# untitled.net
KiCad netlist of a schematic drawn in EAGLE
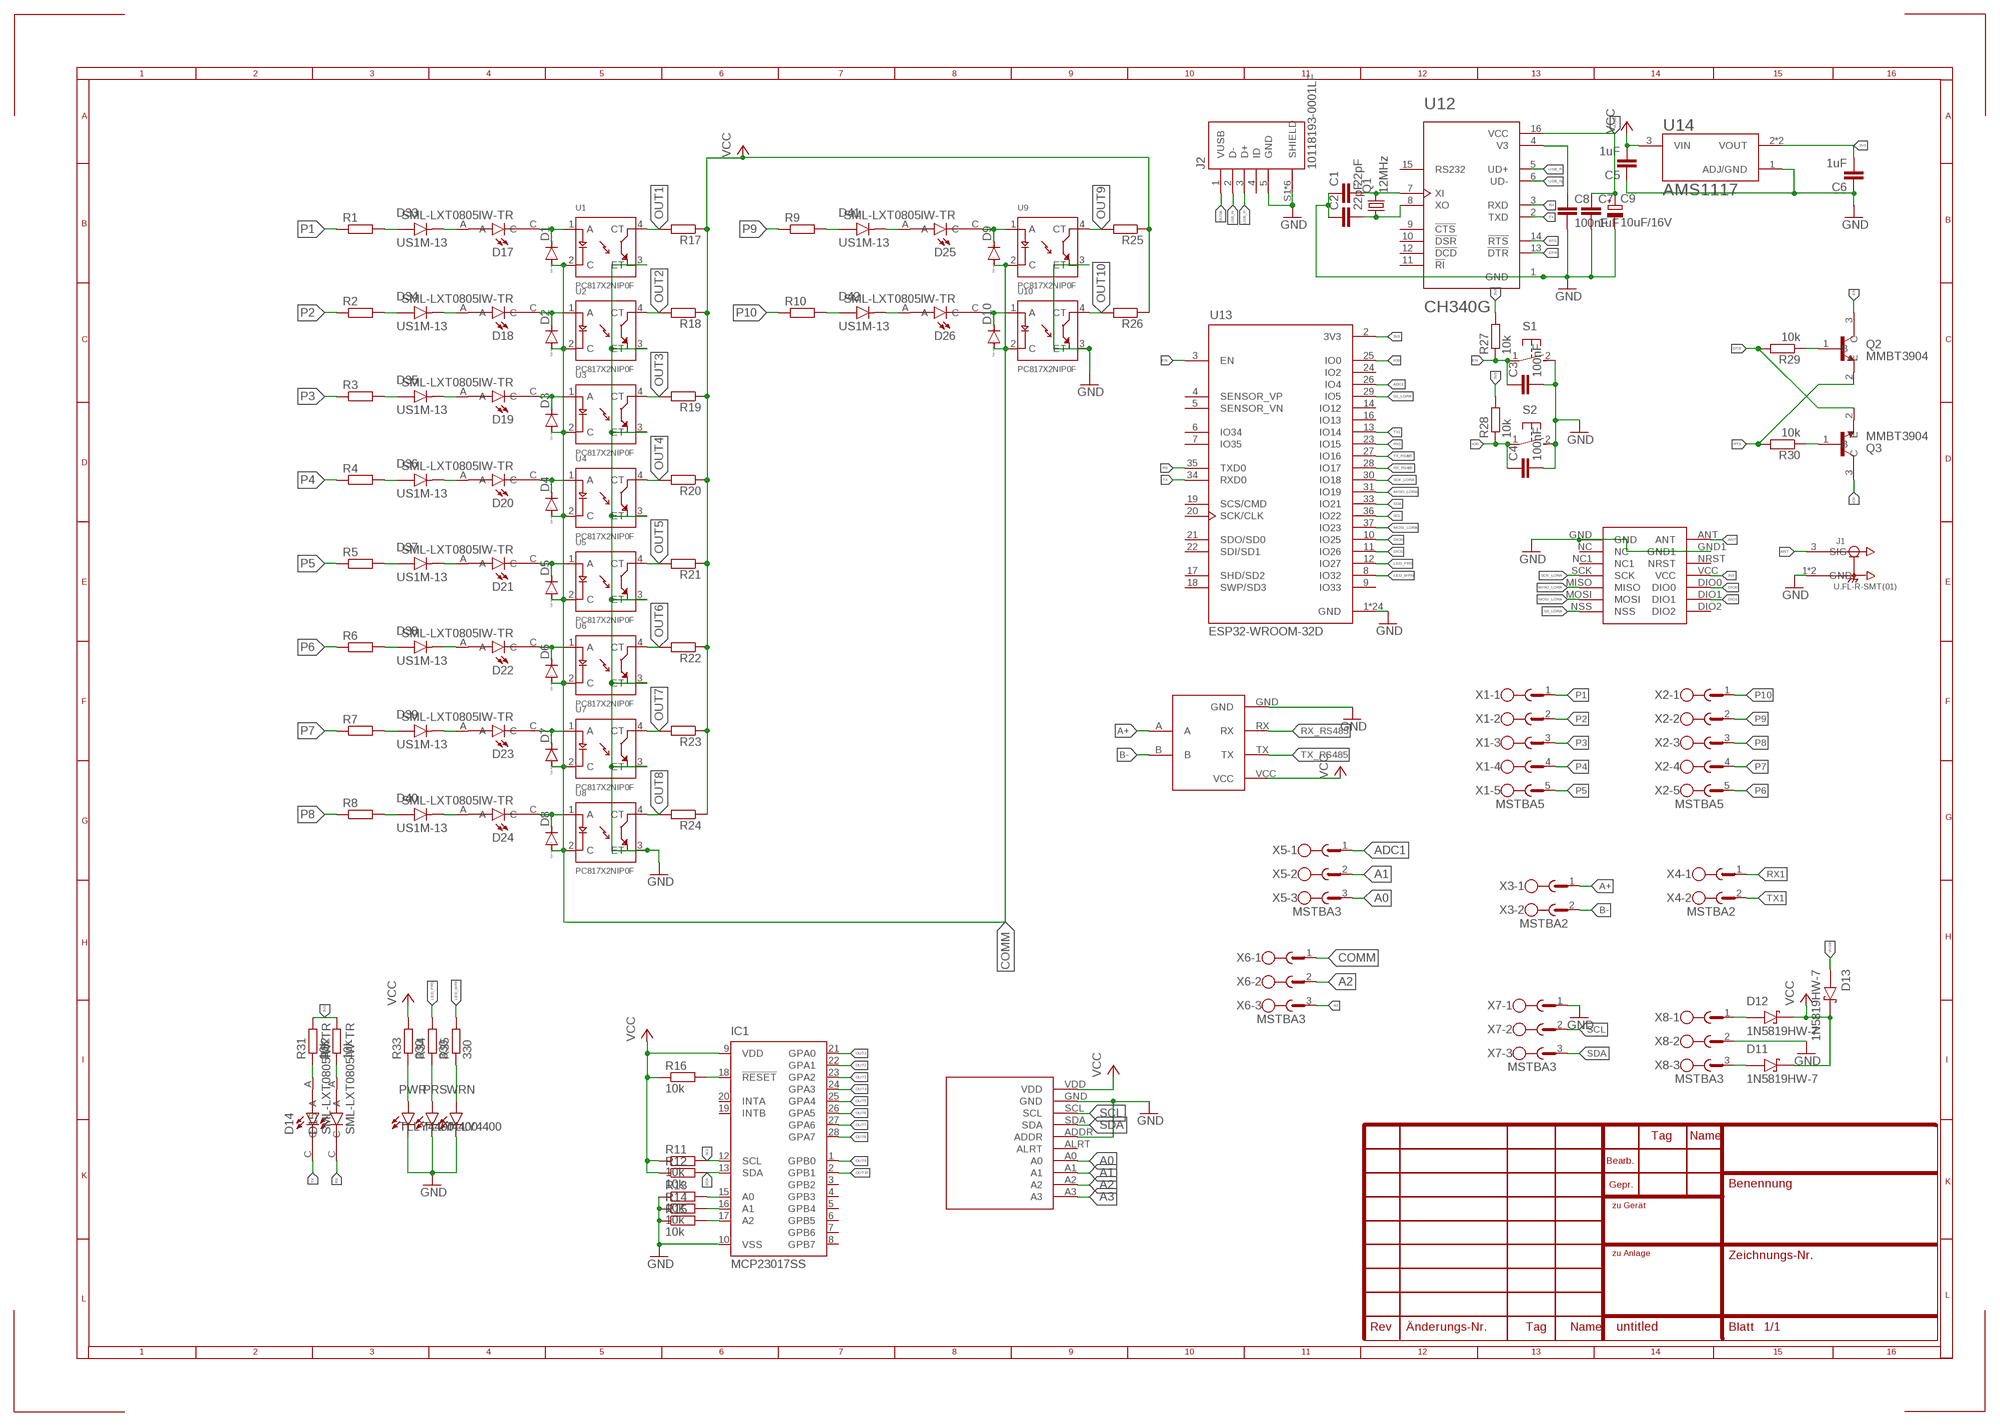
[diagram p0: schematic, sheet 1]

(export (version "E")
  (design (tool "Eeschema 10.0.6"))
  (components
    (comp (ref "ADS1")
      (value "ADS1115")
      (footprint "eagle-import:ADS1115")
      (libsource (lib "eagle-import") (part "ADS1115"))
    )
    (comp (ref "C1")
      (value "22pF")
      (footprint "eagle-import:C0805K")
      (libsource (lib "eagle-import") (part "C-EUC0805K"))
    )
    (comp (ref "C2")
      (value "22pF")
      (footprint "eagle-import:C0805K")
      (libsource (lib "eagle-import") (part "C-EUC0805K"))
    )
    (comp (ref "C3")
      (value "100nF")
      (footprint "eagle-import:C0805K")
      (libsource (lib "eagle-import") (part "C-EUC0805K"))
    )
    (comp (ref "C4")
      (value "100nF")
      (footprint "eagle-import:C0805K")
      (libsource (lib "eagle-import") (part "C-EUC0805K"))
    )
    (comp (ref "C5")
      (value "1uF")
      (footprint "eagle-import:C0805K")
      (libsource (lib "eagle-import") (part "C-EUC0805K"))
    )
    (comp (ref "C6")
      (value "1uF")
      (footprint "eagle-import:C0805K")
      (libsource (lib "eagle-import") (part "C-EUC0805K"))
    )
    (comp (ref "C7")
      (value "1uF")
      (footprint "eagle-import:C0805K")
      (libsource (lib "eagle-import") (part "C-EUC0805K"))
    )
    (comp (ref "C8")
      (value "100nF")
      (footprint "eagle-import:C0805K")
      (libsource (lib "eagle-import") (part "C-EUC0805K"))
    )
    (comp (ref "C9")
      (value "10uF/16V")
      (footprint "eagle-import:153CLV-0505")
      (libsource (lib "eagle-import") (part "CPOL-EU153CLV-0505"))
    )
    (comp (ref "D1")
      (value "DIODE-SOD123")
      (footprint "eagle-import:SOD123")
      (libsource (lib "eagle-import") (part "DIODE-SOD123"))
    )
    (comp (ref "D2")
      (value "DIODE-SOD123")
      (footprint "eagle-import:SOD123")
      (libsource (lib "eagle-import") (part "DIODE-SOD123"))
    )
    (comp (ref "D3")
      (value "DIODE-SOD123")
      (footprint "eagle-import:SOD123")
      (libsource (lib "eagle-import") (part "DIODE-SOD123"))
    )
    (comp (ref "D4")
      (value "DIODE-SOD123")
      (footprint "eagle-import:SOD123")
      (libsource (lib "eagle-import") (part "DIODE-SOD123"))
    )
    (comp (ref "D5")
      (value "DIODE-SOD123")
      (footprint "eagle-import:SOD123")
      (libsource (lib "eagle-import") (part "DIODE-SOD123"))
    )
    (comp (ref "D6")
      (value "DIODE-SOD123")
      (footprint "eagle-import:SOD123")
      (libsource (lib "eagle-import") (part "DIODE-SOD123"))
    )
    (comp (ref "D7")
      (value "DIODE-SOD123")
      (footprint "eagle-import:SOD123")
      (libsource (lib "eagle-import") (part "DIODE-SOD123"))
    )
    (comp (ref "D8")
      (value "DIODE-SOD123")
      (footprint "eagle-import:SOD123")
      (libsource (lib "eagle-import") (part "DIODE-SOD123"))
    )
    (comp (ref "D9")
      (value "DIODE-SOD123")
      (footprint "eagle-import:SOD123")
      (libsource (lib "eagle-import") (part "DIODE-SOD123"))
    )
    (comp (ref "D10")
      (value "DIODE-SOD123")
      (footprint "eagle-import:SOD123")
      (libsource (lib "eagle-import") (part "DIODE-SOD123"))
    )
    (comp (ref "D11")
      (value "1N5819HW-7")
      (footprint "eagle-import:SOD3715X145N")
      (fields (field (name "MF") "Diodes Inc."))
      (libsource (lib "eagle-import") (part "1N5819HW-7"))
    )
    (comp (ref "D12")
      (value "1N5819HW-7")
      (footprint "eagle-import:SOD3715X145N")
      (fields (field (name "MF") "Diodes Inc."))
      (libsource (lib "eagle-import") (part "1N5819HW-7"))
    )
    (comp (ref "D13")
      (value "1N5819HW-7")
      (footprint "eagle-import:SOD3715X145N")
      (fields (field (name "MF") "Diodes Inc."))
      (libsource (lib "eagle-import") (part "1N5819HW-7"))
    )
    (comp (ref "D14")
      (value "SML-LXT0805IW-TR")
      (footprint "eagle-import:LEDC2012X120N")
      (fields (field (name "MF") "Lumex Opto/Components"))
      (libsource (lib "eagle-import") (part "SML-LXT0805IW-TR"))
    )
    (comp (ref "D15")
      (value "SML-LXT0805IW-TR")
      (footprint "eagle-import:LEDC2012X120N")
      (fields (field (name "MF") "Lumex Opto/Components"))
      (libsource (lib "eagle-import") (part "SML-LXT0805IW-TR"))
    )
    (comp (ref "D17")
      (value "SML-LXT0805IW-TR")
      (footprint "eagle-import:LEDC2012X120N")
      (fields (field (name "MF") "Lumex Opto/Components"))
      (libsource (lib "eagle-import") (part "SML-LXT0805IW-TR"))
    )
    (comp (ref "D18")
      (value "SML-LXT0805IW-TR")
      (footprint "eagle-import:LEDC2012X120N")
      (fields (field (name "MF") "Lumex Opto/Components"))
      (libsource (lib "eagle-import") (part "SML-LXT0805IW-TR"))
    )
    (comp (ref "D19")
      (value "SML-LXT0805IW-TR")
      (footprint "eagle-import:LEDC2012X120N")
      (fields (field (name "MF") "Lumex Opto/Components"))
      (libsource (lib "eagle-import") (part "SML-LXT0805IW-TR"))
    )
    (comp (ref "D20")
      (value "SML-LXT0805IW-TR")
      (footprint "eagle-import:LEDC2012X120N")
      (fields (field (name "MF") "Lumex Opto/Components"))
      (libsource (lib "eagle-import") (part "SML-LXT0805IW-TR"))
    )
    (comp (ref "D21")
      (value "SML-LXT0805IW-TR")
      (footprint "eagle-import:LEDC2012X120N")
      (fields (field (name "MF") "Lumex Opto/Components"))
      (libsource (lib "eagle-import") (part "SML-LXT0805IW-TR"))
    )
    (comp (ref "D22")
      (value "SML-LXT0805IW-TR")
      (footprint "eagle-import:LEDC2012X120N")
      (fields (field (name "MF") "Lumex Opto/Components"))
      (libsource (lib "eagle-import") (part "SML-LXT0805IW-TR"))
    )
    (comp (ref "D23")
      (value "SML-LXT0805IW-TR")
      (footprint "eagle-import:LEDC2012X120N")
      (fields (field (name "MF") "Lumex Opto/Components"))
      (libsource (lib "eagle-import") (part "SML-LXT0805IW-TR"))
    )
    (comp (ref "D24")
      (value "SML-LXT0805IW-TR")
      (footprint "eagle-import:LEDC2012X120N")
      (fields (field (name "MF") "Lumex Opto/Components"))
      (libsource (lib "eagle-import") (part "SML-LXT0805IW-TR"))
    )
    (comp (ref "D25")
      (value "SML-LXT0805IW-TR")
      (footprint "eagle-import:LEDC2012X120N")
      (fields (field (name "MF") "Lumex Opto/Components"))
      (libsource (lib "eagle-import") (part "SML-LXT0805IW-TR"))
    )
    (comp (ref "D26")
      (value "SML-LXT0805IW-TR")
      (footprint "eagle-import:LEDC2012X120N")
      (fields (field (name "MF") "Lumex Opto/Components"))
      (libsource (lib "eagle-import") (part "SML-LXT0805IW-TR"))
    )
    (comp (ref "D33")
      (value "US1M-13")
      (footprint "eagle-import:DIOM5226X240N")
      (fields (field (name "MF") "Diodes Incorporated"))
      (libsource (lib "eagle-import") (part "US1M-13"))
    )
    (comp (ref "D34")
      (value "US1M-13")
      (footprint "eagle-import:DIOM5226X240N")
      (fields (field (name "MF") "Diodes Incorporated"))
      (libsource (lib "eagle-import") (part "US1M-13"))
    )
    (comp (ref "D35")
      (value "US1M-13")
      (footprint "eagle-import:DIOM5226X240N")
      (fields (field (name "MF") "Diodes Incorporated"))
      (libsource (lib "eagle-import") (part "US1M-13"))
    )
    (comp (ref "D36")
      (value "US1M-13")
      (footprint "eagle-import:DIOM5226X240N")
      (fields (field (name "MF") "Diodes Incorporated"))
      (libsource (lib "eagle-import") (part "US1M-13"))
    )
    (comp (ref "D37")
      (value "US1M-13")
      (footprint "eagle-import:DIOM5226X240N")
      (fields (field (name "MF") "Diodes Incorporated"))
      (libsource (lib "eagle-import") (part "US1M-13"))
    )
    (comp (ref "D38")
      (value "US1M-13")
      (footprint "eagle-import:DIOM5226X240N")
      (fields (field (name "MF") "Diodes Incorporated"))
      (libsource (lib "eagle-import") (part "US1M-13"))
    )
    (comp (ref "D39")
      (value "US1M-13")
      (footprint "eagle-import:DIOM5226X240N")
      (fields (field (name "MF") "Diodes Incorporated"))
      (libsource (lib "eagle-import") (part "US1M-13"))
    )
    (comp (ref "D40")
      (value "US1M-13")
      (footprint "eagle-import:DIOM5226X240N")
      (fields (field (name "MF") "Diodes Incorporated"))
      (libsource (lib "eagle-import") (part "US1M-13"))
    )
    (comp (ref "D41")
      (value "US1M-13")
      (footprint "eagle-import:DIOM5226X240N")
      (fields (field (name "MF") "Diodes Incorporated"))
      (libsource (lib "eagle-import") (part "US1M-13"))
    )
    (comp (ref "D42")
      (value "US1M-13")
      (footprint "eagle-import:DIOM5226X240N")
      (fields (field (name "MF") "Diodes Incorporated"))
      (libsource (lib "eagle-import") (part "US1M-13"))
    )
    (comp (ref "IC1")
      (value "MCP23017SS")
      (footprint "eagle-import:SSOP28")
      (fields (field (name "MF") "MICROCHIP") (field (name "MPN") "MCP23017-E/SS"))
      (libsource (lib "eagle-import") (part "MCP23017SS"))
    )
    (comp (ref "J1")
      (value "U.FL-R-SMT(01)")
      (footprint "eagle-import:HRS_U.FL-R-SMT(01)")
      (fields (field (name "MF") "Hirose"))
      (libsource (lib "eagle-import") (part "U.FL-R-SMT(01)"))
    )
    (comp (ref "J2")
      (value "10118193-0001LF")
      (footprint "eagle-import:FCI_10118193-0001LF")
      (fields (field (name "MF") "FCI"))
      (libsource (lib "eagle-import") (part "10118193-0001LF"))
    )
    (comp (ref "LORA-NICERF-V1")
      (value "LORA-NICERF-V2")
      (footprint "eagle-import:LORA-NICERF-V2")
      (libsource (lib "eagle-import") (part "LORA-NICERF-V2"))
    )
    (comp (ref "PRS")
      (value "TLLY4400")
      (footprint "eagle-import:LED3MM")
      (fields (field (name "MF") "VISHAY SEMICONDUCTOR"))
      (libsource (lib "eagle-import") (part "TLLY4400"))
    )
    (comp (ref "PWR")
      (value "TLLY4400")
      (footprint "eagle-import:LED3MM")
      (fields (field (name "MF") "VISHAY SEMICONDUCTOR"))
      (libsource (lib "eagle-import") (part "TLLY4400"))
    )
    (comp (ref "Q1")
      (value "12MHz")
      (footprint "eagle-import:SM49")
      (libsource (lib "eagle-import") (part "CRYSTALSM49"))
    )
    (comp (ref "Q2")
      (value "MMBT3904")
      (footprint "eagle-import:SOT95P240X120-3N")
      (fields (field (name "MF") "ON Semiconductor"))
      (libsource (lib "eagle-import") (part "MMBT3904"))
    )
    (comp (ref "Q3")
      (value "MMBT3904")
      (footprint "eagle-import:SOT95P240X120-3N")
      (fields (field (name "MF") "ON Semiconductor"))
      (libsource (lib "eagle-import") (part "MMBT3904"))
    )
    (comp (ref "R1")
      (value "R-EU_0414/15")
      (footprint "eagle-import:0414_15")
      (libsource (lib "eagle-import") (part "R-EU_0414/15"))
    )
    (comp (ref "R2")
      (value "R-EU_0414/15")
      (footprint "eagle-import:0414_15")
      (libsource (lib "eagle-import") (part "R-EU_0414/15"))
    )
    (comp (ref "R3")
      (value "R-EU_0414/15")
      (footprint "eagle-import:0414_15")
      (libsource (lib "eagle-import") (part "R-EU_0414/15"))
    )
    (comp (ref "R4")
      (value "R-EU_0414/15")
      (footprint "eagle-import:0414_15")
      (libsource (lib "eagle-import") (part "R-EU_0414/15"))
    )
    (comp (ref "R5")
      (value "R-EU_0414/15")
      (footprint "eagle-import:0414_15")
      (libsource (lib "eagle-import") (part "R-EU_0414/15"))
    )
    (comp (ref "R6")
      (value "R-EU_0414/15")
      (footprint "eagle-import:0414_15")
      (libsource (lib "eagle-import") (part "R-EU_0414/15"))
    )
    (comp (ref "R7")
      (value "R-EU_0414/15")
      (footprint "eagle-import:0414_15")
      (libsource (lib "eagle-import") (part "R-EU_0414/15"))
    )
    (comp (ref "R8")
      (value "R-EU_0414/15")
      (footprint "eagle-import:0414_15")
      (libsource (lib "eagle-import") (part "R-EU_0414/15"))
    )
    (comp (ref "R9")
      (value "R-EU_0414/15")
      (footprint "eagle-import:0414_15")
      (libsource (lib "eagle-import") (part "R-EU_0414/15"))
    )
    (comp (ref "R10")
      (value "R-EU_0414/15")
      (footprint "eagle-import:0414_15")
      (libsource (lib "eagle-import") (part "R-EU_0414/15"))
    )
    (comp (ref "R11")
      (value "10k")
      (footprint "eagle-import:R0805")
      (libsource (lib "eagle-import") (part "R-EU_R0805"))
    )
    (comp (ref "R12")
      (value "10k")
      (footprint "eagle-import:R0805")
      (libsource (lib "eagle-import") (part "R-EU_R0805"))
    )
    (comp (ref "R13")
      (value "10k")
      (footprint "eagle-import:R0805")
      (libsource (lib "eagle-import") (part "R-EU_R0805"))
    )
    (comp (ref "R14")
      (value "10k")
      (footprint "eagle-import:R0805")
      (libsource (lib "eagle-import") (part "R-EU_R0805"))
    )
    (comp (ref "R15")
      (value "10k")
      (footprint "eagle-import:R0805")
      (libsource (lib "eagle-import") (part "R-EU_R0805"))
    )
    (comp (ref "R16")
      (value "10k")
      (footprint "eagle-import:R0805")
      (libsource (lib "eagle-import") (part "R-EU_R0805"))
    )
    (comp (ref "R17")
      (value "R-EU_R0805")
      (footprint "eagle-import:R0805")
      (libsource (lib "eagle-import") (part "R-EU_R0805"))
    )
    (comp (ref "R18")
      (value "R-EU_R0805")
      (footprint "eagle-import:R0805")
      (libsource (lib "eagle-import") (part "R-EU_R0805"))
    )
    (comp (ref "R19")
      (value "R-EU_R0805")
      (footprint "eagle-import:R0805")
      (libsource (lib "eagle-import") (part "R-EU_R0805"))
    )
    (comp (ref "R20")
      (value "R-EU_R0805")
      (footprint "eagle-import:R0805")
      (libsource (lib "eagle-import") (part "R-EU_R0805"))
    )
    (comp (ref "R21")
      (value "R-EU_R0805")
      (footprint "eagle-import:R0805")
      (libsource (lib "eagle-import") (part "R-EU_R0805"))
    )
    (comp (ref "R22")
      (value "R-EU_R0805")
      (footprint "eagle-import:R0805")
      (libsource (lib "eagle-import") (part "R-EU_R0805"))
    )
    (comp (ref "R23")
      (value "R-EU_R0805")
      (footprint "eagle-import:R0805")
      (libsource (lib "eagle-import") (part "R-EU_R0805"))
    )
    (comp (ref "R24")
      (value "R-EU_R0805")
      (footprint "eagle-import:R0805")
      (libsource (lib "eagle-import") (part "R-EU_R0805"))
    )
    (comp (ref "R25")
      (value "R-EU_R0805")
      (footprint "eagle-import:R0805")
      (libsource (lib "eagle-import") (part "R-EU_R0805"))
    )
    (comp (ref "R26")
      (value "R-EU_R0805")
      (footprint "eagle-import:R0805")
      (libsource (lib "eagle-import") (part "R-EU_R0805"))
    )
    (comp (ref "R27")
      (value "10k")
      (footprint "eagle-import:R0805")
      (libsource (lib "eagle-import") (part "R-EU_R0805"))
    )
    (comp (ref "R28")
      (value "10k")
      (footprint "eagle-import:R0805")
      (libsource (lib "eagle-import") (part "R-EU_R0805"))
    )
    (comp (ref "R29")
      (value "10k")
      (footprint "eagle-import:R0805")
      (libsource (lib "eagle-import") (part "R-EU_R0805"))
    )
    (comp (ref "R30")
      (value "10k")
      (footprint "eagle-import:R0805")
      (libsource (lib "eagle-import") (part "R-EU_R0805"))
    )
    (comp (ref "R31")
      (value "10k")
      (footprint "eagle-import:R0805")
      (libsource (lib "eagle-import") (part "R-EU_R0805"))
    )
    (comp (ref "R32")
      (value "10k")
      (footprint "eagle-import:R0805")
      (libsource (lib "eagle-import") (part "R-EU_R0805"))
    )
    (comp (ref "R33")
      (value "330")
      (footprint "eagle-import:R0805")
      (libsource (lib "eagle-import") (part "R-EU_R0805"))
    )
    (comp (ref "R34")
      (value "330")
      (footprint "eagle-import:R0805")
      (libsource (lib "eagle-import") (part "R-EU_R0805"))
    )
    (comp (ref "R35")
      (value "330")
      (footprint "eagle-import:R0805")
      (libsource (lib "eagle-import") (part "R-EU_R0805"))
    )
    (comp (ref "S1")
      (value "31-XX")
      (footprint "eagle-import:B3F-31XX")
      (fields (field (name "MPN") "B3F-3100"))
      (libsource (lib "eagle-import") (part "31-XX"))
    )
    (comp (ref "S2")
      (value "31-XX")
      (footprint "eagle-import:B3F-31XX")
      (fields (field (name "MPN") "B3F-3100"))
      (libsource (lib "eagle-import") (part "31-XX"))
    )
    (comp (ref "TTL-RS1")
      (value "TTL-RS485")
      (footprint "eagle-import:TTL-RS485")
      (libsource (lib "eagle-import") (part "TTL-RS485"))
    )
    (comp (ref "U1")
      (value "PC817X2NIP0F")
      (footprint "eagle-import:SOT254P975X400-4N")
      (fields (field (name "MF") "Sharp Microelectronics"))
      (libsource (lib "eagle-import") (part "PC817X2NIP0F"))
    )
    (comp (ref "U2")
      (value "PC817X2NIP0F")
      (footprint "eagle-import:SOT254P975X400-4N")
      (fields (field (name "MF") "Sharp Microelectronics"))
      (libsource (lib "eagle-import") (part "PC817X2NIP0F"))
    )
    (comp (ref "U3")
      (value "PC817X2NIP0F")
      (footprint "eagle-import:SOT254P975X400-4N")
      (fields (field (name "MF") "Sharp Microelectronics"))
      (libsource (lib "eagle-import") (part "PC817X2NIP0F"))
    )
    (comp (ref "U4")
      (value "PC817X2NIP0F")
      (footprint "eagle-import:SOT254P975X400-4N")
      (fields (field (name "MF") "Sharp Microelectronics"))
      (libsource (lib "eagle-import") (part "PC817X2NIP0F"))
    )
    (comp (ref "U5")
      (value "PC817X2NIP0F")
      (footprint "eagle-import:SOT254P975X400-4N")
      (fields (field (name "MF") "Sharp Microelectronics"))
      (libsource (lib "eagle-import") (part "PC817X2NIP0F"))
    )
    (comp (ref "U6")
      (value "PC817X2NIP0F")
      (footprint "eagle-import:SOT254P975X400-4N")
      (fields (field (name "MF") "Sharp Microelectronics"))
      (libsource (lib "eagle-import") (part "PC817X2NIP0F"))
    )
    (comp (ref "U7")
      (value "PC817X2NIP0F")
      (footprint "eagle-import:SOT254P975X400-4N")
      (fields (field (name "MF") "Sharp Microelectronics"))
      (libsource (lib "eagle-import") (part "PC817X2NIP0F"))
    )
    (comp (ref "U8")
      (value "PC817X2NIP0F")
      (footprint "eagle-import:SOT254P975X400-4N")
      (fields (field (name "MF") "Sharp Microelectronics"))
      (libsource (lib "eagle-import") (part "PC817X2NIP0F"))
    )
    (comp (ref "U9")
      (value "PC817X2NIP0F")
      (footprint "eagle-import:SOT254P975X400-4N")
      (fields (field (name "MF") "Sharp Microelectronics"))
      (libsource (lib "eagle-import") (part "PC817X2NIP0F"))
    )
    (comp (ref "U10")
      (value "PC817X2NIP0F")
      (footprint "eagle-import:SOT254P975X400-4N")
      (fields (field (name "MF") "Sharp Microelectronics"))
      (libsource (lib "eagle-import") (part "PC817X2NIP0F"))
    )
    (comp (ref "U12")
      (value "CH340G")
      (footprint "eagle-import:SOIC127P600X180-16N")
      (fields (field (name "MF") "WCH") (field (name "MP") "Ch340G"))
      (libsource (lib "eagle-import") (part "CH340G"))
    )
    (comp (ref "U13")
      (value "ESP32-WROOM-32D")
      (footprint "eagle-import:MODULE_ESP32-WROOM-32D")
      (fields (field (name "MF") "Espressif Systems"))
      (libsource (lib "eagle-import") (part "ESP32-WROOM-32D"))
    )
    (comp (ref "U14")
      (value "AMS1117")
      (footprint "eagle-import:SOT229P700X180-4N")
      (fields (field (name "MF") "Advanced Monolithic Systems"))
      (libsource (lib "eagle-import") (part "AMS1117"))
    )
    (comp (ref "WRN")
      (value "TLLY4400")
      (footprint "eagle-import:LED3MM")
      (fields (field (name "MF") "VISHAY SEMICONDUCTOR"))
      (libsource (lib "eagle-import") (part "TLLY4400"))
    )
    (comp (ref "X1")
      (value "MSTBA5")
      (footprint "eagle-import:MSTBA5")
      (fields (field (name "MPN") "1757271"))
      (libsource (lib "eagle-import") (part "MSTBA5"))
    )
    (comp (ref "X2")
      (value "MSTBA5")
      (footprint "eagle-import:MSTBA5")
      (fields (field (name "MPN") "1757271"))
      (libsource (lib "eagle-import") (part "MSTBA5"))
    )
    (comp (ref "X3")
      (value "MSTBA2")
      (footprint "eagle-import:MSTBA2")
      (fields (field (name "MF") "FARNELL") (field (name "MPN") "1757242"))
      (libsource (lib "eagle-import") (part "MSTBA2"))
    )
    (comp (ref "X4")
      (value "MSTBA2")
      (footprint "eagle-import:MSTBA2")
      (fields (field (name "MF") "FARNELL") (field (name "MPN") "1757242"))
      (libsource (lib "eagle-import") (part "MSTBA2"))
    )
    (comp (ref "X5")
      (value "MSTBA3")
      (footprint "eagle-import:MSTBA3")
      (fields (field (name "MF") "FARNELL") (field (name "MPN") "1757255"))
      (libsource (lib "eagle-import") (part "MSTBA3"))
    )
    (comp (ref "X6")
      (value "MSTBA3")
      (footprint "eagle-import:MSTBA3")
      (fields (field (name "MF") "FARNELL") (field (name "MPN") "1757255"))
      (libsource (lib "eagle-import") (part "MSTBA3"))
    )
    (comp (ref "X7")
      (value "MSTBA3")
      (footprint "eagle-import:MSTBA3")
      (fields (field (name "MF") "FARNELL") (field (name "MPN") "1757255"))
      (libsource (lib "eagle-import") (part "MSTBA3"))
    )
    (comp (ref "X8")
      (value "MSTBA3")
      (footprint "eagle-import:MSTBA3")
      (fields (field (name "MF") "FARNELL") (field (name "MPN") "1757255"))
      (libsource (lib "eagle-import") (part "MSTBA3"))
    )
  )
  (nets
    (net (code "1") (name "3V3") (class "Default")
      (node (ref "C6") (pin "2") (pinfunction "2_2") (pintype "passive"))
      (node (ref "LORA-NICERF-V1") (pin "VCC") (pinfunction "VCC_VCC") (pintype "bidirectional"))
      (node (ref "R27") (pin "2") (pinfunction "2_2") (pintype "passive"))
      (node (ref "R28") (pin "2") (pinfunction "2_2") (pintype "passive"))
      (node (ref "R31") (pin "2") (pinfunction "2_2") (pintype "passive"))
      (node (ref "R32") (pin "2") (pinfunction "2_2") (pintype "passive"))
      (node (ref "U13") (pin "2") (pinfunction "3V3_2") (pintype "power_in"))
      (node (ref "U14") (pin "2") (pinfunction "VOUT_2") (pintype "output"))
      (node (ref "U14") (pin "4") (pinfunction "VOUT_4") (pintype "output"))
    )
    (net (code "2") (name "A+") (class "Default")
      (node (ref "TTL-RS1") (pin "A") (pinfunction "A_A") (pintype "bidirectional"))
      (node (ref "X3") (pin "1") (pinfunction "1_1") (pintype "passive"))
    )
    (net (code "3") (name "A0") (class "Default")
      (node (ref "ADS1") (pin "A0") (pinfunction "A0_A0") (pintype "bidirectional"))
      (node (ref "X5") (pin "3") (pinfunction "1_3") (pintype "passive"))
    )
    (net (code "4") (name "A1") (class "Default")
      (node (ref "ADS1") (pin "A1") (pinfunction "A1_A1") (pintype "bidirectional"))
      (node (ref "X5") (pin "2") (pinfunction "1_2") (pintype "passive"))
    )
    (net (code "5") (name "A2") (class "Default")
      (node (ref "ADS1") (pin "A2") (pinfunction "A2_A2") (pintype "bidirectional"))
      (node (ref "X6") (pin "2") (pinfunction "1_2") (pintype "passive"))
    )
    (net (code "6") (name "A3") (class "Default")
      (node (ref "ADS1") (pin "A3") (pinfunction "A3_A3") (pintype "bidirectional"))
      (node (ref "X6") (pin "3") (pinfunction "1_3") (pintype "passive"))
    )
    (net (code "7") (name "ADC1") (class "Default")
      (node (ref "U13") (pin "26") (pinfunction "IO4_26") (pintype "bidirectional"))
      (node (ref "X5") (pin "1") (pinfunction "1_1") (pintype "passive"))
    )
    (net (code "8") (name "ANT") (class "Default")
      (node (ref "J1") (pin "3") (pinfunction "SIG_3") (pintype "passive"))
      (node (ref "LORA-NICERF-V1") (pin "ANT") (pinfunction "ANT_ANT") (pintype "bidirectional"))
    )
    (net (code "9") (name "B-") (class "Default")
      (node (ref "TTL-RS1") (pin "B") (pinfunction "B_B") (pintype "bidirectional"))
      (node (ref "X3") (pin "2") (pinfunction "1_2") (pintype "passive"))
    )
    (net (code "10") (name "COMM") (class "Default")
      (node (ref "D1") (pin "A") (pinfunction "A_A") (pintype "passive"))
      (node (ref "D10") (pin "A") (pinfunction "A_A") (pintype "passive"))
      (node (ref "D2") (pin "A") (pinfunction "A_A") (pintype "passive"))
      (node (ref "D3") (pin "A") (pinfunction "A_A") (pintype "passive"))
      (node (ref "D4") (pin "A") (pinfunction "A_A") (pintype "passive"))
      (node (ref "D5") (pin "A") (pinfunction "A_A") (pintype "passive"))
      (node (ref "D6") (pin "A") (pinfunction "A_A") (pintype "passive"))
      (node (ref "D7") (pin "A") (pinfunction "A_A") (pintype "passive"))
      (node (ref "D8") (pin "A") (pinfunction "A_A") (pintype "passive"))
      (node (ref "D9") (pin "A") (pinfunction "A_A") (pintype "passive"))
      (node (ref "U1") (pin "2") (pinfunction "C_2") (pintype "passive"))
      (node (ref "U10") (pin "2") (pinfunction "C_2") (pintype "passive"))
      (node (ref "U2") (pin "2") (pinfunction "C_2") (pintype "passive"))
      (node (ref "U3") (pin "2") (pinfunction "C_2") (pintype "passive"))
      (node (ref "U4") (pin "2") (pinfunction "C_2") (pintype "passive"))
      (node (ref "U5") (pin "2") (pinfunction "C_2") (pintype "passive"))
      (node (ref "U6") (pin "2") (pinfunction "C_2") (pintype "passive"))
      (node (ref "U7") (pin "2") (pinfunction "C_2") (pintype "passive"))
      (node (ref "U8") (pin "2") (pinfunction "C_2") (pintype "passive"))
      (node (ref "U9") (pin "2") (pinfunction "C_2") (pintype "passive"))
      (node (ref "X6") (pin "1") (pinfunction "1_1") (pintype "passive"))
    )
    (net (code "11") (name "DIO0") (class "Default")
      (node (ref "LORA-NICERF-V1") (pin "DIO0") (pinfunction "DIO0_DIO0") (pintype "bidirectional"))
      (node (ref "U13") (pin "10") (pinfunction "IO25_10") (pintype "bidirectional"))
    )
    (net (code "12") (name "DIO1") (class "Default")
      (node (ref "LORA-NICERF-V1") (pin "DIO1") (pinfunction "DIO1_DIO1") (pintype "bidirectional"))
      (node (ref "U13") (pin "11") (pinfunction "IO26_11") (pintype "bidirectional"))
    )
    (net (code "13") (name "DTR") (class "Default")
      (node (ref "Q3") (pin "2") (pinfunction "E_2") (pintype "passive"))
      (node (ref "R29") (pin "2") (pinfunction "2_2") (pintype "passive"))
      (node (ref "U12") (pin "13") (pinfunction "~{DTR}_13") (pintype "output"))
    )
    (net (code "14") (name "EN") (class "Default")
      (node (ref "C3") (pin "1") (pinfunction "1_1") (pintype "passive"))
      (node (ref "Q2") (pin "3") (pinfunction "C_3") (pintype "passive"))
      (node (ref "R27") (pin "1") (pinfunction "1_1") (pintype "passive"))
      (node (ref "S1") (pin "1") (pinfunction "P_1") (pintype "passive"))
      (node (ref "U13") (pin "3") (pinfunction "EN_3") (pintype "input"))
    )
    (net (code "15") (name "GND") (class "Default")
      (node (ref "ADS1") (pin "ADDR") (pinfunction "ADDR_ADDR") (pintype "bidirectional"))
      (node (ref "ADS1") (pin "GND") (pinfunction "GND_GND") (pintype "bidirectional"))
      (node (ref "C1") (pin "1") (pinfunction "1_1") (pintype "passive"))
      (node (ref "C2") (pin "1") (pinfunction "1_1") (pintype "passive"))
      (node (ref "C3") (pin "2") (pinfunction "2_2") (pintype "passive"))
      (node (ref "C4") (pin "2") (pinfunction "2_2") (pintype "passive"))
      (node (ref "C5") (pin "1") (pinfunction "1_1") (pintype "passive"))
      (node (ref "C6") (pin "1") (pinfunction "1_1") (pintype "passive"))
      (node (ref "C7") (pin "2") (pinfunction "2_2") (pintype "passive"))
      (node (ref "C8") (pin "2") (pinfunction "2_2") (pintype "passive"))
      (node (ref "C9") (pin "-") (pinfunction "-_-") (pintype "passive"))
      (node (ref "IC1") (pin "10") (pinfunction "VSS_10") (pintype "power_in"))
      (node (ref "J1") (pin "1") (pinfunction "GND_1") (pintype "passive"))
      (node (ref "J1") (pin "2") (pinfunction "GND_2") (pintype "passive"))
      (node (ref "J2") (pin "5") (pinfunction "GND_5") (pintype "passive"))
      (node (ref "J2") (pin "S1") (pinfunction "SHIELD_S1") (pintype "passive"))
      (node (ref "J2") (pin "S2") (pinfunction "SHIELD_S2") (pintype "passive"))
      (node (ref "J2") (pin "S3") (pinfunction "SHIELD_S3") (pintype "passive"))
      (node (ref "J2") (pin "S4") (pinfunction "SHIELD_S4") (pintype "passive"))
      (node (ref "J2") (pin "S5") (pinfunction "SHIELD_S5") (pintype "passive"))
      (node (ref "J2") (pin "S6") (pinfunction "SHIELD_S6") (pintype "passive"))
      (node (ref "LORA-NICERF-V1") (pin "GND") (pinfunction "GND_GND") (pintype "bidirectional"))
      (node (ref "LORA-NICERF-V1") (pin "GND1") (pinfunction "GND1_GND1") (pintype "bidirectional"))
      (node (ref "PRS") (pin "K") (pinfunction "C_K") (pintype "passive"))
      (node (ref "PWR") (pin "K") (pinfunction "C_K") (pintype "passive"))
      (node (ref "R13") (pin "1") (pinfunction "1_1") (pintype "passive"))
      (node (ref "R14") (pin "1") (pinfunction "1_1") (pintype "passive"))
      (node (ref "R15") (pin "1") (pinfunction "1_1") (pintype "passive"))
      (node (ref "S1") (pin "2") (pinfunction "S_2") (pintype "passive"))
      (node (ref "S2") (pin "2") (pinfunction "S_2") (pintype "passive"))
      (node (ref "TTL-RS1") (pin "GND") (pinfunction "GND_GND") (pintype "bidirectional"))
      (node (ref "U1") (pin "3") (pinfunction "ET_3") (pintype "passive"))
      (node (ref "U10") (pin "3") (pinfunction "ET_3") (pintype "passive"))
      (node (ref "U12") (pin "1") (pinfunction "GND_1") (pintype "power_in"))
      (node (ref "U13") (pin "1") (pinfunction "GND_1") (pintype "power_in"))
      (node (ref "U13") (pin "15") (pinfunction "GND_15") (pintype "power_in"))
      (node (ref "U13") (pin "38") (pinfunction "GND_38") (pintype "power_in"))
      (node (ref "U13") (pin "39_1") (pinfunction "GND_39_1") (pintype "power_in"))
      (node (ref "U13") (pin "39_10") (pinfunction "GND_39_10") (pintype "power_in"))
      (node (ref "U13") (pin "39_11") (pinfunction "GND_39_11") (pintype "power_in"))
      (node (ref "U13") (pin "39_12") (pinfunction "GND_39_12") (pintype "power_in"))
      (node (ref "U13") (pin "39_13") (pinfunction "GND_39_13") (pintype "power_in"))
      (node (ref "U13") (pin "39_14") (pinfunction "GND_39_14") (pintype "power_in"))
      (node (ref "U13") (pin "39_15") (pinfunction "GND_39_15") (pintype "power_in"))
      (node (ref "U13") (pin "39_16") (pinfunction "GND_39_16") (pintype "power_in"))
      (node (ref "U13") (pin "39_17") (pinfunction "GND_39_17") (pintype "power_in"))
      (node (ref "U13") (pin "39_18") (pinfunction "GND_39_18") (pintype "power_in"))
      (node (ref "U13") (pin "39_19") (pinfunction "GND_39_19") (pintype "power_in"))
      (node (ref "U13") (pin "39_2") (pinfunction "GND_39_2") (pintype "power_in"))
      (node (ref "U13") (pin "39_20") (pinfunction "GND_39_20") (pintype "power_in"))
      (node (ref "U13") (pin "39_21") (pinfunction "GND_39_21") (pintype "power_in"))
      (node (ref "U13") (pin "39_3") (pinfunction "GND_39_3") (pintype "power_in"))
      (node (ref "U13") (pin "39_4") (pinfunction "GND_39_4") (pintype "power_in"))
      (node (ref "U13") (pin "39_5") (pinfunction "GND_39_5") (pintype "power_in"))
      (node (ref "U13") (pin "39_6") (pinfunction "GND_39_6") (pintype "power_in"))
      (node (ref "U13") (pin "39_7") (pinfunction "GND_39_7") (pintype "power_in"))
      (node (ref "U13") (pin "39_8") (pinfunction "GND_39_8") (pintype "power_in"))
      (node (ref "U13") (pin "39_9") (pinfunction "GND_39_9") (pintype "power_in"))
      (node (ref "U14") (pin "1") (pinfunction "ADJ/GND_1") (pintype "power_in"))
      (node (ref "U2") (pin "3") (pinfunction "ET_3") (pintype "passive"))
      (node (ref "U3") (pin "3") (pinfunction "ET_3") (pintype "passive"))
      (node (ref "U4") (pin "3") (pinfunction "ET_3") (pintype "passive"))
      (node (ref "U5") (pin "3") (pinfunction "ET_3") (pintype "passive"))
      (node (ref "U6") (pin "3") (pinfunction "ET_3") (pintype "passive"))
      (node (ref "U7") (pin "3") (pinfunction "ET_3") (pintype "passive"))
      (node (ref "U8") (pin "3") (pinfunction "ET_3") (pintype "passive"))
      (node (ref "U9") (pin "3") (pinfunction "ET_3") (pintype "passive"))
      (node (ref "WRN") (pin "K") (pinfunction "C_K") (pintype "passive"))
      (node (ref "X7") (pin "1") (pinfunction "1_1") (pintype "passive"))
      (node (ref "X8") (pin "2") (pinfunction "1_2") (pintype "passive"))
    )
    (net (code "16") (name "IO0") (class "Default")
      (node (ref "C4") (pin "1") (pinfunction "1_1") (pintype "passive"))
      (node (ref "Q3") (pin "3") (pinfunction "C_3") (pintype "passive"))
      (node (ref "R28") (pin "1") (pinfunction "1_1") (pintype "passive"))
      (node (ref "S2") (pin "1") (pinfunction "P_1") (pintype "passive"))
      (node (ref "U13") (pin "25") (pinfunction "IO0_25") (pintype "bidirectional"))
    )
    (net (code "17") (name "LED_PRS") (class "Default")
      (node (ref "R34") (pin "2") (pinfunction "2_2") (pintype "passive"))
      (node (ref "U13") (pin "12") (pinfunction "IO27_12") (pintype "bidirectional"))
    )
    (net (code "18") (name "LED_WRN") (class "Default")
      (node (ref "R35") (pin "2") (pinfunction "2_2") (pintype "passive"))
      (node (ref "U13") (pin "8") (pinfunction "IO32_8") (pintype "bidirectional"))
    )
    (net (code "19") (name "MISO_LORA") (class "Default")
      (node (ref "LORA-NICERF-V1") (pin "MISO") (pinfunction "MISO_MISO") (pintype "bidirectional"))
      (node (ref "U13") (pin "31") (pinfunction "IO19_31") (pintype "bidirectional"))
    )
    (net (code "20") (name "MOSI_LORA") (class "Default")
      (node (ref "LORA-NICERF-V1") (pin "MOSI") (pinfunction "MOSI_MOSI") (pintype "bidirectional"))
      (node (ref "U13") (pin "37") (pinfunction "IO23_37") (pintype "bidirectional"))
    )
    (net (code "21") (name "Net-(D12-PadA)") (class "Default")
      (node (ref "D12") (pin "A") (pinfunction "A_A") (pintype "passive"))
      (node (ref "X8") (pin "1") (pinfunction "1_1") (pintype "passive"))
    )
    (net (code "22") (name "Net-(D14-PadA)") (class "Default")
      (node (ref "D14") (pin "A") (pinfunction "A_A") (pintype "passive"))
      (node (ref "R31") (pin "1") (pinfunction "1_1") (pintype "passive"))
    )
    (net (code "23") (name "Net-(D15-PadA)") (class "Default")
      (node (ref "D15") (pin "A") (pinfunction "A_A") (pintype "passive"))
      (node (ref "R32") (pin "1") (pinfunction "1_1") (pintype "passive"))
    )
    (net (code "24") (name "Net-(D33-K)") (class "Default")
      (node (ref "D17") (pin "A") (pinfunction "A_A") (pintype "passive"))
      (node (ref "D33") (pin "C") (pinfunction "K_C") (pintype "passive"))
    )
    (net (code "25") (name "Net-(D33-PadA)") (class "Default")
      (node (ref "D33") (pin "A") (pinfunction "A_A") (pintype "passive"))
      (node (ref "R1") (pin "2") (pinfunction "2_2") (pintype "passive"))
    )
    (net (code "26") (name "Net-(D34-K)") (class "Default")
      (node (ref "D18") (pin "A") (pinfunction "A_A") (pintype "passive"))
      (node (ref "D34") (pin "C") (pinfunction "K_C") (pintype "passive"))
    )
    (net (code "27") (name "Net-(D34-PadA)") (class "Default")
      (node (ref "D34") (pin "A") (pinfunction "A_A") (pintype "passive"))
      (node (ref "R2") (pin "2") (pinfunction "2_2") (pintype "passive"))
    )
    (net (code "28") (name "Net-(D35-K)") (class "Default")
      (node (ref "D19") (pin "A") (pinfunction "A_A") (pintype "passive"))
      (node (ref "D35") (pin "C") (pinfunction "K_C") (pintype "passive"))
    )
    (net (code "29") (name "Net-(D35-PadA)") (class "Default")
      (node (ref "D35") (pin "A") (pinfunction "A_A") (pintype "passive"))
      (node (ref "R3") (pin "2") (pinfunction "2_2") (pintype "passive"))
    )
    (net (code "30") (name "Net-(D36-K)") (class "Default")
      (node (ref "D20") (pin "A") (pinfunction "A_A") (pintype "passive"))
      (node (ref "D36") (pin "C") (pinfunction "K_C") (pintype "passive"))
    )
    (net (code "31") (name "Net-(D36-PadA)") (class "Default")
      (node (ref "D36") (pin "A") (pinfunction "A_A") (pintype "passive"))
      (node (ref "R4") (pin "2") (pinfunction "2_2") (pintype "passive"))
    )
    (net (code "32") (name "Net-(D37-K)") (class "Default")
      (node (ref "D21") (pin "A") (pinfunction "A_A") (pintype "passive"))
      (node (ref "D37") (pin "C") (pinfunction "K_C") (pintype "passive"))
    )
    (net (code "33") (name "Net-(D37-PadA)") (class "Default")
      (node (ref "D37") (pin "A") (pinfunction "A_A") (pintype "passive"))
      (node (ref "R5") (pin "2") (pinfunction "2_2") (pintype "passive"))
    )
    (net (code "34") (name "Net-(D38-K)") (class "Default")
      (node (ref "D22") (pin "A") (pinfunction "A_A") (pintype "passive"))
      (node (ref "D38") (pin "C") (pinfunction "K_C") (pintype "passive"))
    )
    (net (code "35") (name "Net-(D38-PadA)") (class "Default")
      (node (ref "D38") (pin "A") (pinfunction "A_A") (pintype "passive"))
      (node (ref "R6") (pin "2") (pinfunction "2_2") (pintype "passive"))
    )
    (net (code "36") (name "Net-(D39-K)") (class "Default")
      (node (ref "D23") (pin "A") (pinfunction "A_A") (pintype "passive"))
      (node (ref "D39") (pin "C") (pinfunction "K_C") (pintype "passive"))
    )
    (net (code "37") (name "Net-(D39-PadA)") (class "Default")
      (node (ref "D39") (pin "A") (pinfunction "A_A") (pintype "passive"))
      (node (ref "R7") (pin "2") (pinfunction "2_2") (pintype "passive"))
    )
    (net (code "38") (name "Net-(D40-K)") (class "Default")
      (node (ref "D24") (pin "A") (pinfunction "A_A") (pintype "passive"))
      (node (ref "D40") (pin "C") (pinfunction "K_C") (pintype "passive"))
    )
    (net (code "39") (name "Net-(D40-PadA)") (class "Default")
      (node (ref "D40") (pin "A") (pinfunction "A_A") (pintype "passive"))
      (node (ref "R8") (pin "2") (pinfunction "2_2") (pintype "passive"))
    )
    (net (code "40") (name "Net-(D41-K)") (class "Default")
      (node (ref "D25") (pin "A") (pinfunction "A_A") (pintype "passive"))
      (node (ref "D41") (pin "C") (pinfunction "K_C") (pintype "passive"))
    )
    (net (code "41") (name "Net-(D41-PadA)") (class "Default")
      (node (ref "D41") (pin "A") (pinfunction "A_A") (pintype "passive"))
      (node (ref "R9") (pin "2") (pinfunction "2_2") (pintype "passive"))
    )
    (net (code "42") (name "Net-(D42-K)") (class "Default")
      (node (ref "D26") (pin "A") (pinfunction "A_A") (pintype "passive"))
      (node (ref "D42") (pin "C") (pinfunction "K_C") (pintype "passive"))
    )
    (net (code "43") (name "Net-(D42-PadA)") (class "Default")
      (node (ref "D42") (pin "A") (pinfunction "A_A") (pintype "passive"))
      (node (ref "R10") (pin "2") (pinfunction "2_2") (pintype "passive"))
    )
    (net (code "44") (name "Net-(IC1-A0)") (class "Default")
      (node (ref "IC1") (pin "15") (pinfunction "A0_15") (pintype "input"))
      (node (ref "R13") (pin "2") (pinfunction "2_2") (pintype "passive"))
    )
    (net (code "45") (name "Net-(IC1-A1)") (class "Default")
      (node (ref "IC1") (pin "16") (pinfunction "A1_16") (pintype "input"))
      (node (ref "R14") (pin "2") (pinfunction "2_2") (pintype "passive"))
    )
    (net (code "46") (name "Net-(IC1-A2)") (class "Default")
      (node (ref "IC1") (pin "17") (pinfunction "A2_17") (pintype "input"))
      (node (ref "R15") (pin "2") (pinfunction "2_2") (pintype "passive"))
    )
    (net (code "47") (name "Net-(IC1-~{RESET})") (class "Default")
      (node (ref "IC1") (pin "18") (pinfunction "~{RESET}_18") (pintype "input"))
      (node (ref "R16") (pin "2") (pinfunction "2_2") (pintype "passive"))
    )
    (net (code "48") (name "Net-(PRS-PadA)") (class "Default")
      (node (ref "PRS") (pin "A") (pinfunction "A_A") (pintype "passive"))
      (node (ref "R34") (pin "1") (pinfunction "1_1") (pintype "passive"))
    )
    (net (code "49") (name "Net-(PWR-PadA)") (class "Default")
      (node (ref "PWR") (pin "A") (pinfunction "A_A") (pintype "passive"))
      (node (ref "R33") (pin "1") (pinfunction "1_1") (pintype "passive"))
    )
    (net (code "50") (name "Net-(Q2-B)") (class "Default")
      (node (ref "Q2") (pin "1") (pinfunction "B_1") (pintype "passive"))
      (node (ref "R29") (pin "1") (pinfunction "1_1") (pintype "passive"))
    )
    (net (code "51") (name "Net-(Q3-B)") (class "Default")
      (node (ref "Q3") (pin "1") (pinfunction "B_1") (pintype "passive"))
      (node (ref "R30") (pin "1") (pinfunction "1_1") (pintype "passive"))
    )
    (net (code "52") (name "Net-(R35-Pad1)") (class "Default")
      (node (ref "R35") (pin "1") (pinfunction "1_1") (pintype "passive"))
      (node (ref "WRN") (pin "A") (pinfunction "A_A") (pintype "passive"))
    )
    (net (code "53") (name "Net-(U1-A)") (class "Default")
      (node (ref "D1") (pin "C") (pinfunction "C_C") (pintype "passive"))
      (node (ref "D17") (pin "C") (pinfunction "C_C") (pintype "passive"))
      (node (ref "U1") (pin "1") (pinfunction "A_1") (pintype "passive"))
    )
    (net (code "54") (name "Net-(U2-A)") (class "Default")
      (node (ref "D18") (pin "C") (pinfunction "C_C") (pintype "passive"))
      (node (ref "D2") (pin "C") (pinfunction "C_C") (pintype "passive"))
      (node (ref "U2") (pin "1") (pinfunction "A_1") (pintype "passive"))
    )
    (net (code "55") (name "Net-(U3-A)") (class "Default")
      (node (ref "D19") (pin "C") (pinfunction "C_C") (pintype "passive"))
      (node (ref "D3") (pin "C") (pinfunction "C_C") (pintype "passive"))
      (node (ref "U3") (pin "1") (pinfunction "A_1") (pintype "passive"))
    )
    (net (code "56") (name "Net-(U4-A)") (class "Default")
      (node (ref "D20") (pin "C") (pinfunction "C_C") (pintype "passive"))
      (node (ref "D4") (pin "C") (pinfunction "C_C") (pintype "passive"))
      (node (ref "U4") (pin "1") (pinfunction "A_1") (pintype "passive"))
    )
    (net (code "57") (name "Net-(U5-A)") (class "Default")
      (node (ref "D21") (pin "C") (pinfunction "C_C") (pintype "passive"))
      (node (ref "D5") (pin "C") (pinfunction "C_C") (pintype "passive"))
      (node (ref "U5") (pin "1") (pinfunction "A_1") (pintype "passive"))
    )
    (net (code "58") (name "Net-(U6-A)") (class "Default")
      (node (ref "D22") (pin "C") (pinfunction "C_C") (pintype "passive"))
      (node (ref "D6") (pin "C") (pinfunction "C_C") (pintype "passive"))
      (node (ref "U6") (pin "1") (pinfunction "A_1") (pintype "passive"))
    )
    (net (code "59") (name "Net-(U7-A)") (class "Default")
      (node (ref "D23") (pin "C") (pinfunction "C_C") (pintype "passive"))
      (node (ref "D7") (pin "C") (pinfunction "C_C") (pintype "passive"))
      (node (ref "U7") (pin "1") (pinfunction "A_1") (pintype "passive"))
    )
    (net (code "60") (name "Net-(U8-A)") (class "Default")
      (node (ref "D24") (pin "C") (pinfunction "C_C") (pintype "passive"))
      (node (ref "D8") (pin "C") (pinfunction "C_C") (pintype "passive"))
      (node (ref "U8") (pin "1") (pinfunction "A_1") (pintype "passive"))
    )
    (net (code "61") (name "Net-(U9-A)") (class "Default")
      (node (ref "D25") (pin "C") (pinfunction "C_C") (pintype "passive"))
      (node (ref "D9") (pin "C") (pinfunction "C_C") (pintype "passive"))
      (node (ref "U9") (pin "1") (pinfunction "A_1") (pintype "passive"))
    )
    (net (code "62") (name "Net-(U10-A)") (class "Default")
      (node (ref "D10") (pin "C") (pinfunction "C_C") (pintype "passive"))
      (node (ref "D26") (pin "C") (pinfunction "C_C") (pintype "passive"))
      (node (ref "U10") (pin "1") (pinfunction "A_1") (pintype "passive"))
    )
    (net (code "63") (name "Net-(U12-V3)") (class "Default")
      (node (ref "C8") (pin "1") (pinfunction "1_1") (pintype "passive"))
      (node (ref "U12") (pin "4") (pinfunction "V3_4") (pintype "power_in"))
    )
    (net (code "64") (name "Net-(U12-XI)") (class "Default")
      (node (ref "C1") (pin "2") (pinfunction "2_2") (pintype "passive"))
      (node (ref "Q1") (pin "2") (pinfunction "2_2") (pintype "passive"))
      (node (ref "U12") (pin "7") (pinfunction "XI_7") (pintype "input"))
    )
    (net (code "65") (name "Net-(U12-XO)") (class "Default")
      (node (ref "C2") (pin "2") (pinfunction "2_2") (pintype "passive"))
      (node (ref "Q1") (pin "1") (pinfunction "1_1") (pintype "passive"))
      (node (ref "U12") (pin "8") (pinfunction "XO_8") (pintype "output"))
    )
    (net (code "66") (name "Net-(X8C-1)") (class "Default")
      (node (ref "D11") (pin "A") (pinfunction "A_A") (pintype "passive"))
      (node (ref "X8") (pin "3") (pinfunction "1_3") (pintype "passive"))
    )
    (net (code "67") (name "OUT1") (class "Default")
      (node (ref "IC1") (pin "21") (pinfunction "GPA0_21") (pintype "bidirectional"))
      (node (ref "R17") (pin "2") (pinfunction "2_2") (pintype "passive"))
      (node (ref "U1") (pin "4") (pinfunction "CT_4") (pintype "passive"))
    )
    (net (code "68") (name "OUT2") (class "Default")
      (node (ref "IC1") (pin "22") (pinfunction "GPA1_22") (pintype "bidirectional"))
      (node (ref "R18") (pin "2") (pinfunction "2_2") (pintype "passive"))
      (node (ref "U2") (pin "4") (pinfunction "CT_4") (pintype "passive"))
    )
    (net (code "69") (name "OUT3") (class "Default")
      (node (ref "IC1") (pin "23") (pinfunction "GPA2_23") (pintype "bidirectional"))
      (node (ref "R19") (pin "2") (pinfunction "2_2") (pintype "passive"))
      (node (ref "U3") (pin "4") (pinfunction "CT_4") (pintype "passive"))
    )
    (net (code "70") (name "OUT4") (class "Default")
      (node (ref "IC1") (pin "24") (pinfunction "GPA3_24") (pintype "bidirectional"))
      (node (ref "R20") (pin "2") (pinfunction "2_2") (pintype "passive"))
      (node (ref "U4") (pin "4") (pinfunction "CT_4") (pintype "passive"))
    )
    (net (code "71") (name "OUT5") (class "Default")
      (node (ref "IC1") (pin "25") (pinfunction "GPA4_25") (pintype "bidirectional"))
      (node (ref "R21") (pin "2") (pinfunction "2_2") (pintype "passive"))
      (node (ref "U5") (pin "4") (pinfunction "CT_4") (pintype "passive"))
    )
    (net (code "72") (name "OUT6") (class "Default")
      (node (ref "IC1") (pin "26") (pinfunction "GPA5_26") (pintype "bidirectional"))
      (node (ref "R22") (pin "2") (pinfunction "2_2") (pintype "passive"))
      (node (ref "U6") (pin "4") (pinfunction "CT_4") (pintype "passive"))
    )
    (net (code "73") (name "OUT7") (class "Default")
      (node (ref "IC1") (pin "27") (pinfunction "GPA6_27") (pintype "bidirectional"))
      (node (ref "R23") (pin "2") (pinfunction "2_2") (pintype "passive"))
      (node (ref "U7") (pin "4") (pinfunction "CT_4") (pintype "passive"))
    )
    (net (code "74") (name "OUT8") (class "Default")
      (node (ref "IC1") (pin "28") (pinfunction "GPA7_28") (pintype "bidirectional"))
      (node (ref "R24") (pin "2") (pinfunction "2_2") (pintype "passive"))
      (node (ref "U8") (pin "4") (pinfunction "CT_4") (pintype "passive"))
    )
    (net (code "75") (name "OUT9") (class "Default")
      (node (ref "IC1") (pin "1") (pinfunction "GPB0_1") (pintype "bidirectional"))
      (node (ref "R25") (pin "2") (pinfunction "2_2") (pintype "passive"))
      (node (ref "U9") (pin "4") (pinfunction "CT_4") (pintype "passive"))
    )
    (net (code "76") (name "OUT10") (class "Default")
      (node (ref "IC1") (pin "2") (pinfunction "GPB1_2") (pintype "bidirectional"))
      (node (ref "R26") (pin "2") (pinfunction "2_2") (pintype "passive"))
      (node (ref "U10") (pin "4") (pinfunction "CT_4") (pintype "passive"))
    )
    (net (code "77") (name "P1") (class "Default")
      (node (ref "R1") (pin "1") (pinfunction "1_1") (pintype "passive"))
      (node (ref "X1") (pin "1") (pinfunction "1_1") (pintype "passive"))
    )
    (net (code "78") (name "P2") (class "Default")
      (node (ref "R2") (pin "1") (pinfunction "1_1") (pintype "passive"))
      (node (ref "X1") (pin "2") (pinfunction "1_2") (pintype "passive"))
    )
    (net (code "79") (name "P3") (class "Default")
      (node (ref "R3") (pin "1") (pinfunction "1_1") (pintype "passive"))
      (node (ref "X1") (pin "3") (pinfunction "1_3") (pintype "passive"))
    )
    (net (code "80") (name "P4") (class "Default")
      (node (ref "R4") (pin "1") (pinfunction "1_1") (pintype "passive"))
      (node (ref "X1") (pin "4") (pinfunction "1_4") (pintype "passive"))
    )
    (net (code "81") (name "P5") (class "Default")
      (node (ref "R5") (pin "1") (pinfunction "1_1") (pintype "passive"))
      (node (ref "X1") (pin "5") (pinfunction "1_5") (pintype "passive"))
    )
    (net (code "82") (name "P6") (class "Default")
      (node (ref "R6") (pin "1") (pinfunction "1_1") (pintype "passive"))
      (node (ref "X2") (pin "5") (pinfunction "1_5") (pintype "passive"))
    )
    (net (code "83") (name "P7") (class "Default")
      (node (ref "R7") (pin "1") (pinfunction "1_1") (pintype "passive"))
      (node (ref "X2") (pin "4") (pinfunction "1_4") (pintype "passive"))
    )
    (net (code "84") (name "P8") (class "Default")
      (node (ref "R8") (pin "1") (pinfunction "1_1") (pintype "passive"))
      (node (ref "X2") (pin "3") (pinfunction "1_3") (pintype "passive"))
    )
    (net (code "85") (name "P9") (class "Default")
      (node (ref "R9") (pin "1") (pinfunction "1_1") (pintype "passive"))
      (node (ref "X2") (pin "2") (pinfunction "1_2") (pintype "passive"))
    )
    (net (code "86") (name "P10") (class "Default")
      (node (ref "R10") (pin "1") (pinfunction "1_1") (pintype "passive"))
      (node (ref "X2") (pin "1") (pinfunction "1_1") (pintype "passive"))
    )
    (net (code "87") (name "RTS") (class "Default")
      (node (ref "Q2") (pin "2") (pinfunction "E_2") (pintype "passive"))
      (node (ref "R30") (pin "2") (pinfunction "2_2") (pintype "passive"))
      (node (ref "U12") (pin "14") (pinfunction "~{RTS}_14") (pintype "output"))
    )
    (net (code "88") (name "RX") (class "Default")
      (node (ref "D15") (pin "C") (pinfunction "C_C") (pintype "passive"))
      (node (ref "U12") (pin "3") (pinfunction "RXD_3") (pintype "input"))
      (node (ref "U13") (pin "35") (pinfunction "TXD0_35") (pintype "bidirectional"))
    )
    (net (code "89") (name "RX1") (class "Default")
      (node (ref "U13") (pin "23") (pinfunction "IO15_23") (pintype "bidirectional"))
      (node (ref "X4") (pin "1") (pinfunction "1_1") (pintype "passive"))
    )
    (net (code "90") (name "RX_RS485") (class "Default")
      (node (ref "TTL-RS1") (pin "RX") (pinfunction "RX_RX") (pintype "bidirectional"))
      (node (ref "U13") (pin "28") (pinfunction "IO17_28") (pintype "bidirectional"))
    )
    (net (code "91") (name "SCK_LORA") (class "Default")
      (node (ref "LORA-NICERF-V1") (pin "SCK") (pinfunction "SCK_SCK") (pintype "bidirectional"))
      (node (ref "U13") (pin "30") (pinfunction "IO18_30") (pintype "bidirectional"))
    )
    (net (code "92") (name "SCL") (class "Default")
      (node (ref "ADS1") (pin "SCL") (pinfunction "SCL_SCL") (pintype "bidirectional"))
      (node (ref "IC1") (pin "12") (pinfunction "SCL_12") (pintype "input"))
      (node (ref "R11") (pin "2") (pinfunction "2_2") (pintype "passive"))
      (node (ref "U13") (pin "36") (pinfunction "IO22_36") (pintype "bidirectional"))
      (node (ref "X7") (pin "2") (pinfunction "1_2") (pintype "passive"))
    )
    (net (code "93") (name "SDA") (class "Default")
      (node (ref "ADS1") (pin "SDA") (pinfunction "SDA_SDA") (pintype "bidirectional"))
      (node (ref "IC1") (pin "13") (pinfunction "SDA_13") (pintype "bidirectional"))
      (node (ref "R12") (pin "2") (pinfunction "2_2") (pintype "passive"))
      (node (ref "U13") (pin "33") (pinfunction "IO21_33") (pintype "bidirectional"))
      (node (ref "X7") (pin "3") (pinfunction "1_3") (pintype "passive"))
    )
    (net (code "94") (name "SS_LORA") (class "Default")
      (node (ref "LORA-NICERF-V1") (pin "NSS") (pinfunction "NSS_NSS") (pintype "bidirectional"))
      (node (ref "U13") (pin "29") (pinfunction "IO5_29") (pintype "bidirectional"))
    )
    (net (code "95") (name "TX") (class "Default")
      (node (ref "D14") (pin "C") (pinfunction "C_C") (pintype "passive"))
      (node (ref "U12") (pin "2") (pinfunction "TXD_2") (pintype "output"))
      (node (ref "U13") (pin "34") (pinfunction "RXD0_34") (pintype "bidirectional"))
    )
    (net (code "96") (name "TX1") (class "Default")
      (node (ref "U13") (pin "13") (pinfunction "IO14_13") (pintype "bidirectional"))
      (node (ref "X4") (pin "2") (pinfunction "1_2") (pintype "passive"))
    )
    (net (code "97") (name "TX_RS485") (class "Default")
      (node (ref "TTL-RS1") (pin "TX") (pinfunction "TX_TX") (pintype "bidirectional"))
      (node (ref "U13") (pin "27") (pinfunction "IO16_27") (pintype "bidirectional"))
    )
    (net (code "98") (name "USB_N") (class "Default")
      (node (ref "J2") (pin "2") (pinfunction "D-_2") (pintype "passive"))
      (node (ref "U12") (pin "6") (pinfunction "UD-_6") (pintype "bidirectional"))
    )
    (net (code "99") (name "USB_P") (class "Default")
      (node (ref "J2") (pin "3") (pinfunction "D+_3") (pintype "passive"))
      (node (ref "U12") (pin "5") (pinfunction "UD+_5") (pintype "bidirectional"))
    )
    (net (code "100") (name "VCC") (class "Default")
      (node (ref "ADS1") (pin "VDD") (pinfunction "VDD_VDD") (pintype "bidirectional"))
      (node (ref "C5") (pin "2") (pinfunction "2_2") (pintype "passive"))
      (node (ref "D11") (pin "C") (pinfunction "K_C") (pintype "passive"))
      (node (ref "D12") (pin "C") (pinfunction "K_C") (pintype "passive"))
      (node (ref "D13") (pin "C") (pinfunction "K_C") (pintype "passive"))
      (node (ref "IC1") (pin "9") (pinfunction "VDD_9") (pintype "power_in"))
      (node (ref "R11") (pin "1") (pinfunction "1_1") (pintype "passive"))
      (node (ref "R12") (pin "1") (pinfunction "1_1") (pintype "passive"))
      (node (ref "R16") (pin "1") (pinfunction "1_1") (pintype "passive"))
      (node (ref "R17") (pin "1") (pinfunction "1_1") (pintype "passive"))
      (node (ref "R18") (pin "1") (pinfunction "1_1") (pintype "passive"))
      (node (ref "R19") (pin "1") (pinfunction "1_1") (pintype "passive"))
      (node (ref "R20") (pin "1") (pinfunction "1_1") (pintype "passive"))
      (node (ref "R21") (pin "1") (pinfunction "1_1") (pintype "passive"))
      (node (ref "R22") (pin "1") (pinfunction "1_1") (pintype "passive"))
      (node (ref "R23") (pin "1") (pinfunction "1_1") (pintype "passive"))
      (node (ref "R24") (pin "1") (pinfunction "1_1") (pintype "passive"))
      (node (ref "R25") (pin "1") (pinfunction "1_1") (pintype "passive"))
      (node (ref "R26") (pin "1") (pinfunction "1_1") (pintype "passive"))
      (node (ref "R33") (pin "2") (pinfunction "2_2") (pintype "passive"))
      (node (ref "TTL-RS1") (pin "VCC") (pinfunction "VCC_VCC") (pintype "bidirectional"))
      (node (ref "U14") (pin "3") (pinfunction "VIN_3") (pintype "input"))
    )
    (net (code "101") (name "VUSB") (class "Default")
      (node (ref "C7") (pin "1") (pinfunction "1_1") (pintype "passive"))
      (node (ref "C9") (pin "+") (pinfunction "+_+") (pintype "passive"))
      (node (ref "D13") (pin "A") (pinfunction "A_A") (pintype "passive"))
      (node (ref "J2") (pin "1") (pinfunction "VUSB_1") (pintype "passive"))
      (node (ref "U12") (pin "16") (pinfunction "VCC_16") (pintype "power_in"))
    )
    (net (code "102") (name "unconnected-(ADS1-PadALRT)") (class "Default")
      (node (ref "ADS1") (pin "ALRT") (pinfunction "ALRT_ALRT") (pintype "bidirectional"))
    )
    (net (code "103") (name "unconnected-(IC1-GPB2-Pad3)") (class "Default")
      (node (ref "IC1") (pin "3") (pinfunction "GPB2_3") (pintype "bidirectional"))
    )
    (net (code "104") (name "unconnected-(IC1-GPB3-Pad4)") (class "Default")
      (node (ref "IC1") (pin "4") (pinfunction "GPB3_4") (pintype "bidirectional"))
    )
    (net (code "105") (name "unconnected-(IC1-GPB4-Pad5)") (class "Default")
      (node (ref "IC1") (pin "5") (pinfunction "GPB4_5") (pintype "bidirectional"))
    )
    (net (code "106") (name "unconnected-(IC1-GPB5-Pad6)") (class "Default")
      (node (ref "IC1") (pin "6") (pinfunction "GPB5_6") (pintype "bidirectional"))
    )
    (net (code "107") (name "unconnected-(IC1-GPB6-Pad7)") (class "Default")
      (node (ref "IC1") (pin "7") (pinfunction "GPB6_7") (pintype "bidirectional"))
    )
    (net (code "108") (name "unconnected-(IC1-GPB7-Pad8)") (class "Default")
      (node (ref "IC1") (pin "8") (pinfunction "GPB7_8") (pintype "bidirectional"))
    )
    (net (code "109") (name "unconnected-(IC1-INTA-Pad20)") (class "Default")
      (node (ref "IC1") (pin "20") (pinfunction "INTA_20") (pintype "output"))
    )
    (net (code "110") (name "unconnected-(IC1-INTB-Pad19)") (class "Default")
      (node (ref "IC1") (pin "19") (pinfunction "INTB_19") (pintype "output"))
    )
    (net (code "111") (name "unconnected-(J2-ID-Pad4)") (class "Default")
      (node (ref "J2") (pin "4") (pinfunction "ID_4") (pintype "passive"))
    )
    (net (code "112") (name "unconnected-(LORA-NICERF-V1-PadDIO2)") (class "Default")
      (node (ref "LORA-NICERF-V1") (pin "DIO2") (pinfunction "DIO2_DIO2") (pintype "bidirectional"))
    )
    (net (code "113") (name "unconnected-(LORA-NICERF-V1-PadNC)") (class "Default")
      (node (ref "LORA-NICERF-V1") (pin "NC") (pinfunction "NC_NC") (pintype "bidirectional"))
    )
    (net (code "114") (name "unconnected-(LORA-NICERF-V1-PadNC1)") (class "Default")
      (node (ref "LORA-NICERF-V1") (pin "NC1") (pinfunction "NC1_NC1") (pintype "bidirectional"))
    )
    (net (code "115") (name "unconnected-(LORA-NICERF-V1-PadNRST)") (class "Default")
      (node (ref "LORA-NICERF-V1") (pin "NRST") (pinfunction "NRST_NRST") (pintype "bidirectional"))
    )
    (net (code "116") (name "unconnected-(U12-RS232-Pad15)") (class "Default")
      (node (ref "U12") (pin "15") (pinfunction "RS232_15") (pintype "input"))
    )
    (net (code "117") (name "unconnected-(U12-~{CTS}-Pad9)") (class "Default")
      (node (ref "U12") (pin "9") (pinfunction "~{CTS}_9") (pintype "input"))
    )
    (net (code "118") (name "unconnected-(U12-~{DCD}-Pad12)") (class "Default")
      (node (ref "U12") (pin "12") (pinfunction "~{DCD}_12") (pintype "input"))
    )
    (net (code "119") (name "unconnected-(U12-~{DSR}-Pad10)") (class "Default")
      (node (ref "U12") (pin "10") (pinfunction "~{DSR}_10") (pintype "input"))
    )
    (net (code "120") (name "unconnected-(U12-~{RI}-Pad11)") (class "Default")
      (node (ref "U12") (pin "11") (pinfunction "~{RI}_11") (pintype "input"))
    )
    (net (code "121") (name "unconnected-(U13-IO2-Pad24)") (class "Default")
      (node (ref "U13") (pin "24") (pinfunction "IO2_24") (pintype "bidirectional"))
    )
    (net (code "122") (name "unconnected-(U13-IO12-Pad14)") (class "Default")
      (node (ref "U13") (pin "14") (pinfunction "IO12_14") (pintype "bidirectional"))
    )
    (net (code "123") (name "unconnected-(U13-IO13-Pad16)") (class "Default")
      (node (ref "U13") (pin "16") (pinfunction "IO13_16") (pintype "bidirectional"))
    )
    (net (code "124") (name "unconnected-(U13-IO33-Pad9)") (class "Default")
      (node (ref "U13") (pin "9") (pinfunction "IO33_9") (pintype "bidirectional"))
    )
    (net (code "125") (name "unconnected-(U13-IO34-Pad6)") (class "Default")
      (node (ref "U13") (pin "6") (pinfunction "IO34_6") (pintype "input"))
    )
    (net (code "126") (name "unconnected-(U13-IO35-Pad7)") (class "Default")
      (node (ref "U13") (pin "7") (pinfunction "IO35_7") (pintype "input"))
    )
    (net (code "127") (name "unconnected-(U13-SCK{slash}CLK-Pad20)") (class "Default")
      (node (ref "U13") (pin "20") (pinfunction "SCK/CLK_20") (pintype "bidirectional"))
    )
    (net (code "128") (name "unconnected-(U13-SCS{slash}CMD-Pad19)") (class "Default")
      (node (ref "U13") (pin "19") (pinfunction "SCS/CMD_19") (pintype "bidirectional"))
    )
    (net (code "129") (name "unconnected-(U13-SDI{slash}SD1-Pad22)") (class "Default")
      (node (ref "U13") (pin "22") (pinfunction "SDI/SD1_22") (pintype "bidirectional"))
    )
    (net (code "130") (name "unconnected-(U13-SDO{slash}SD0-Pad21)") (class "Default")
      (node (ref "U13") (pin "21") (pinfunction "SDO/SD0_21") (pintype "bidirectional"))
    )
    (net (code "131") (name "unconnected-(U13-SENSOR_VN-Pad5)") (class "Default")
      (node (ref "U13") (pin "5") (pinfunction "SENSOR_VN_5") (pintype "input"))
    )
    (net (code "132") (name "unconnected-(U13-SENSOR_VP-Pad4)") (class "Default")
      (node (ref "U13") (pin "4") (pinfunction "SENSOR_VP_4") (pintype "input"))
    )
    (net (code "133") (name "unconnected-(U13-SHD{slash}SD2-Pad17)") (class "Default")
      (node (ref "U13") (pin "17") (pinfunction "SHD/SD2_17") (pintype "bidirectional"))
    )
    (net (code "134") (name "unconnected-(U13-SWP{slash}SD3-Pad18)") (class "Default")
      (node (ref "U13") (pin "18") (pinfunction "SWP/SD3_18") (pintype "bidirectional"))
    )
  )
)
